# STM8_LQFP64_DEVELOPMENT_BOARD.net
KiCad netlist of a schematic drawn in Altium Designer
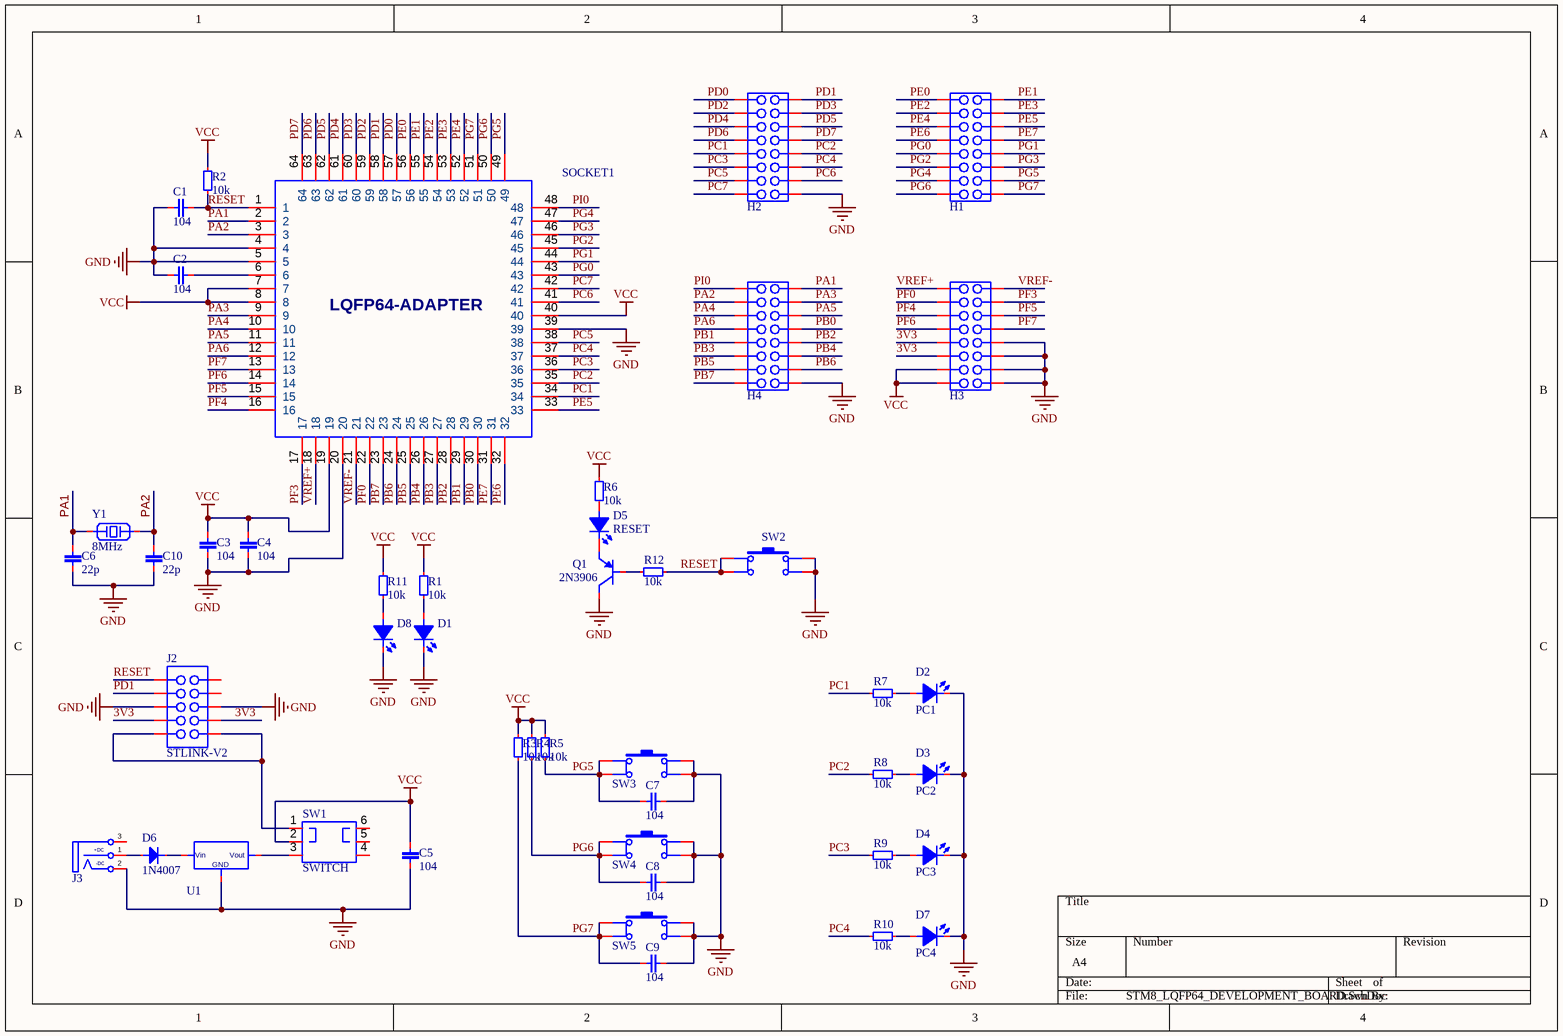
[diagram p0: STM8_LQFP64_DEVELOPMENT_BOARD.SchDoc]

(export (version "E")
  (design (tool "Eeschema 10.0.6"))
  (components
    (comp (ref "C1")
      (value "104")
      (footprint "C0805")
      (libsource (lib "MyAltiumLibrary") (part "Capacitors(SMD)"))
    )
    (comp (ref "C2")
      (value "104")
      (footprint "C0805")
      (libsource (lib "MyAltiumLibrary") (part "Capacitors(SMD)"))
    )
    (comp (ref "C3") (value "104") (footprint "C1812") (libsource (lib "") (part "Capacitors(SMD)_1")))
    (comp (ref "C4") (value "104") (footprint "C0805") (libsource (lib "") (part "Capacitors(SMD)_1")))
    (comp (ref "C5") (value "104") (footprint "C1812") (libsource (lib "") (part "Capacitors(SMD)_1")))
    (comp (ref "C6") (value "22p") (footprint "C0805") (libsource (lib "") (part "Capacitors(SMD)_1")))
    (comp (ref "C7")
      (value "104")
      (footprint "C0805")
      (libsource (lib "MyAltiumLibrary") (part "Capacitors(SMD)"))
    )
    (comp (ref "C8")
      (value "104")
      (footprint "C0805")
      (libsource (lib "MyAltiumLibrary") (part "Capacitors(SMD)"))
    )
    (comp (ref "C9")
      (value "104")
      (footprint "C0805")
      (libsource (lib "MyAltiumLibrary") (part "Capacitors(SMD)"))
    )
    (comp (ref "C10") (value "22p") (footprint "C0805") (libsource (lib "") (part "Capacitors(SMD)_1")))
    (comp (ref "D1")
      (value "POWER")
      (footprint "L0805RED")
      (libsource (lib "MyAltiumLibrary") (part "LED0805"))
    )
    (comp (ref "D2")
      (value "PC1")
      (footprint "L0805RED")
      (libsource (lib "MyAltiumLibrary") (part "LED0805"))
    )
    (comp (ref "D3")
      (value "PC2")
      (footprint "L0805RED")
      (libsource (lib "MyAltiumLibrary") (part "LED0805"))
    )
    (comp (ref "D4")
      (value "PC3")
      (footprint "L0805RED")
      (libsource (lib "MyAltiumLibrary") (part "LED0805"))
    )
    (comp (ref "D5")
      (value "RESET")
      (footprint "L0805RED")
      (libsource (lib "MyAltiumLibrary") (part "LED0805"))
    )
    (comp (ref "D6")
      (value "1N4007")
      (footprint "DO-214AC")
      (libsource (lib "MyAltiumLibrary") (part "Diode-1N4007"))
    )
    (comp (ref "D7")
      (value "PC4")
      (footprint "L0805RED")
      (libsource (lib "MyAltiumLibrary") (part "LED0805"))
    )
    (comp (ref "D8")
      (value "POWER")
      (footprint "L0805RED")
      (libsource (lib "MyAltiumLibrary") (part "LED0805"))
    )
    (comp (ref "H1")
      (value "HEADER-MALE-DOUBLE")
      (footprint "HEADER-MALE-DOUBLE-16PINS-2.54MM")
      (libsource (lib "MyAltiumLibrary") (part "HEADER-MALE-DOUBLE-16PINS-2.54MM"))
    )
    (comp (ref "H2")
      (value "HEADER-MALE-DOUBLE")
      (footprint "HEADER-MALE-DOUBLE-16PINS-2.54MM")
      (libsource (lib "MyAltiumLibrary") (part "HEADER-MALE-DOUBLE-16PINS-2.54MM"))
    )
    (comp (ref "H3")
      (value "HEADER-MALE-DOUBLE")
      (footprint "HEADER-MALE-DOUBLE-16PINS-2.54MM")
      (libsource (lib "MyAltiumLibrary") (part "HEADER-MALE-DOUBLE-16PINS-2.54MM"))
    )
    (comp (ref "H4")
      (value "HEADER-MALE-DOUBLE")
      (footprint "HEADER-MALE-DOUBLE-16PINS-2.54MM")
      (libsource (lib "MyAltiumLibrary") (part "HEADER-MALE-DOUBLE-16PINS-2.54MM"))
    )
    (comp (ref "J2")
      (value "STLINK-V2")
      (footprint "IDC_CONNECTOR_10x2.54")
      (libsource (lib "MyAltiumLibrary") (part "IDC_2.54_5x2"))
    )
    (comp (ref "J3")
      (value "Connector")
      (footprint "DC_K375A_Power")
      (libsource (lib "MyAltiumLibrary") (part "JackDC"))
    )
    (comp (ref "Q1")
      (value "2N3906")
      (footprint "SOT23-3")
      (libsource (lib "MyAltiumLibrary") (part "Transistor-2N3906 (SOT-23)"))
    )
    (comp (ref "R1") (value "10k") (footprint "R0805") (libsource (lib "") (part "Resistors-SMD_2")))
    (comp (ref "R2")
      (value "10k")
      (footprint "R0805")
      (libsource (lib "MyAltiumLibrary") (part "Resistors-SMD"))
    )
    (comp (ref "R3")
      (value "10k")
      (footprint "R0805")
      (libsource (lib "MyAltiumLibrary") (part "Resistors-SMD"))
    )
    (comp (ref "R4")
      (value "10k")
      (footprint "R0805")
      (libsource (lib "MyAltiumLibrary") (part "Resistors-SMD"))
    )
    (comp (ref "R5")
      (value "10k")
      (footprint "R0805")
      (libsource (lib "MyAltiumLibrary") (part "Resistors-SMD"))
    )
    (comp (ref "R6") (value "10k") (footprint "R0805") (libsource (lib "") (part "Resistors-SMD_2")))
    (comp (ref "R7") (value "10k") (footprint "R0805") (libsource (lib "") (part "Resistors-SMD_1")))
    (comp (ref "R8") (value "10k") (footprint "R0805") (libsource (lib "") (part "Resistors-SMD_1")))
    (comp (ref "R9") (value "10k") (footprint "R0805") (libsource (lib "") (part "Resistors-SMD_1")))
    (comp (ref "R10") (value "10k") (footprint "R0805") (libsource (lib "") (part "Resistors-SMD_1")))
    (comp (ref "R11") (value "10k") (footprint "R0805") (libsource (lib "") (part "Resistors-SMD_2")))
    (comp (ref "R12") (value "10k") (footprint "R0805") (libsource (lib "") (part "Resistors-SMD_1")))
    (comp (ref "SOCKET1")
      (value "STM8 MICROCONTROLLER")
      (footprint "SOCKET-ADAPTER-OTQ-64-05-03")
      (libsource (lib "MyAltiumLibrary") (part "Mcu-SOCKET-ADAPTER-OTQ-64-05-03"))
    )
    (comp (ref "SW1")
      (value "SWITCH")
      (footprint "SWITCH 5.8x5.8 6 PINS")
      (libsource (lib "MyAltiumLibrary") (part "SWITCH-DPDT"))
    )
    (comp (ref "SW2")
      (value "RESET")
      (footprint "BUTTON_HOLE_4.3mm")
      (libsource (lib "MyAltiumLibrary") (part "Button Hole"))
    )
    (comp (ref "SW3")
      (value "PG5")
      (footprint "BUTTON_HOLE_4.3mm")
      (libsource (lib "MyAltiumLibrary") (part "Button Hole"))
    )
    (comp (ref "SW4")
      (value "PG6")
      (footprint "BUTTON_HOLE_4.3mm")
      (libsource (lib "MyAltiumLibrary") (part "Button Hole"))
    )
    (comp (ref "SW5")
      (value "PG7")
      (footprint "BUTTON_HOLE_4.3mm")
      (libsource (lib "MyAltiumLibrary") (part "Button Hole"))
    )
    (comp (ref "U1")
      (value "AMS1117")
      (footprint "SOT223-3")
      (libsource (lib "MyAltiumLibrary") (part "Ic-AMS1117(SOT-223)"))
    )
    (comp (ref "Y1")
      (value "8MHz")
      (footprint "HC-49_THROUGH")
      (libsource (lib "MyAltiumLibrary") (part "Crystal"))
    )
  )
  (nets
    (net (code "1") (name "/3V3") (class "Default")
      (node (ref "H3") (pin "11") (pinfunction "11_11") (pintype "passive"))
      (node (ref "H3") (pin "9") (pinfunction "9_9") (pintype "passive"))
      (node (ref "J2") (pin "7") (pinfunction "7_7") (pintype "passive"))
      (node (ref "J2") (pin "8") (pinfunction "8_8") (pintype "passive"))
    )
    (net (code "2") (name "/PA1") (class "Default")
      (node (ref "C6") (pin "2") (pinfunction "2_2") (pintype "passive"))
      (node (ref "H4") (pin "2") (pinfunction "2_2") (pintype "passive"))
      (node (ref "SOCKET1") (pin "2") (pinfunction "2_2") (pintype "passive"))
      (node (ref "Y1") (pin "1") (pinfunction "1_1") (pintype "passive"))
    )
    (net (code "3") (name "/PA2") (class "Default")
      (node (ref "C10") (pin "2") (pinfunction "2_2") (pintype "passive"))
      (node (ref "H4") (pin "3") (pinfunction "3_3") (pintype "passive"))
      (node (ref "SOCKET1") (pin "3") (pinfunction "3_3") (pintype "passive"))
      (node (ref "Y1") (pin "2") (pinfunction "2_2") (pintype "passive"))
    )
    (net (code "4") (name "/PA3") (class "Default")
      (node (ref "H4") (pin "4") (pinfunction "4_4") (pintype "passive"))
      (node (ref "SOCKET1") (pin "9") (pinfunction "9_9") (pintype "passive"))
    )
    (net (code "5") (name "/PA4") (class "Default")
      (node (ref "H4") (pin "5") (pinfunction "5_5") (pintype "passive"))
      (node (ref "SOCKET1") (pin "10") (pinfunction "10_10") (pintype "passive"))
    )
    (net (code "6") (name "/PA5") (class "Default")
      (node (ref "H4") (pin "6") (pinfunction "6_6") (pintype "passive"))
      (node (ref "SOCKET1") (pin "11") (pinfunction "11_11") (pintype "passive"))
    )
    (net (code "7") (name "/PA6") (class "Default")
      (node (ref "H4") (pin "7") (pinfunction "7_7") (pintype "passive"))
      (node (ref "SOCKET1") (pin "12") (pinfunction "12_12") (pintype "passive"))
    )
    (net (code "8") (name "/PB0") (class "Default")
      (node (ref "H4") (pin "8") (pinfunction "8_8") (pintype "passive"))
      (node (ref "SOCKET1") (pin "30") (pinfunction "30_30") (pintype "passive"))
    )
    (net (code "9") (name "/PB1") (class "Default")
      (node (ref "H4") (pin "9") (pinfunction "9_9") (pintype "passive"))
      (node (ref "SOCKET1") (pin "29") (pinfunction "29_29") (pintype "passive"))
    )
    (net (code "10") (name "/PB2") (class "Default")
      (node (ref "H4") (pin "10") (pinfunction "10_10") (pintype "passive"))
      (node (ref "SOCKET1") (pin "28") (pinfunction "28_28") (pintype "passive"))
    )
    (net (code "11") (name "/PB3") (class "Default")
      (node (ref "H4") (pin "11") (pinfunction "11_11") (pintype "passive"))
      (node (ref "SOCKET1") (pin "27") (pinfunction "27_27") (pintype "passive"))
    )
    (net (code "12") (name "/PB4") (class "Default")
      (node (ref "H4") (pin "12") (pinfunction "12_12") (pintype "passive"))
      (node (ref "SOCKET1") (pin "26") (pinfunction "26_26") (pintype "passive"))
    )
    (net (code "13") (name "/PB5") (class "Default")
      (node (ref "H4") (pin "13") (pinfunction "13_13") (pintype "passive"))
      (node (ref "SOCKET1") (pin "25") (pinfunction "25_25") (pintype "passive"))
    )
    (net (code "14") (name "/PB6") (class "Default")
      (node (ref "H4") (pin "14") (pinfunction "14_14") (pintype "passive"))
      (node (ref "SOCKET1") (pin "24") (pinfunction "24_24") (pintype "passive"))
    )
    (net (code "15") (name "/PB7") (class "Default")
      (node (ref "H4") (pin "15") (pinfunction "15_15") (pintype "passive"))
      (node (ref "SOCKET1") (pin "23") (pinfunction "23_23") (pintype "passive"))
    )
    (net (code "16") (name "/PC1") (class "Default")
      (node (ref "H2") (pin "9") (pinfunction "9_9") (pintype "passive"))
      (node (ref "R7") (pin "2") (pinfunction "2_2") (pintype "passive"))
      (node (ref "SOCKET1") (pin "34") (pinfunction "34_34") (pintype "passive"))
    )
    (net (code "17") (name "/PC2") (class "Default")
      (node (ref "H2") (pin "10") (pinfunction "10_10") (pintype "passive"))
      (node (ref "R8") (pin "2") (pinfunction "2_2") (pintype "passive"))
      (node (ref "SOCKET1") (pin "35") (pinfunction "35_35") (pintype "passive"))
    )
    (net (code "18") (name "/PC3") (class "Default")
      (node (ref "H2") (pin "11") (pinfunction "11_11") (pintype "passive"))
      (node (ref "R9") (pin "2") (pinfunction "2_2") (pintype "passive"))
      (node (ref "SOCKET1") (pin "36") (pinfunction "36_36") (pintype "passive"))
    )
    (net (code "19") (name "/PC4") (class "Default")
      (node (ref "H2") (pin "12") (pinfunction "12_12") (pintype "passive"))
      (node (ref "R10") (pin "2") (pinfunction "2_2") (pintype "passive"))
      (node (ref "SOCKET1") (pin "37") (pinfunction "37_37") (pintype "passive"))
    )
    (net (code "20") (name "/PC5") (class "Default")
      (node (ref "H2") (pin "13") (pinfunction "13_13") (pintype "passive"))
      (node (ref "SOCKET1") (pin "38") (pinfunction "38_38") (pintype "passive"))
    )
    (net (code "21") (name "/PC6") (class "Default")
      (node (ref "H2") (pin "14") (pinfunction "14_14") (pintype "passive"))
      (node (ref "SOCKET1") (pin "41") (pinfunction "41_41") (pintype "passive"))
    )
    (net (code "22") (name "/PC7") (class "Default")
      (node (ref "H2") (pin "15") (pinfunction "15_15") (pintype "passive"))
      (node (ref "SOCKET1") (pin "42") (pinfunction "42_42") (pintype "passive"))
    )
    (net (code "23") (name "/PD0") (class "Default")
      (node (ref "H2") (pin "1") (pinfunction "1_1") (pintype "passive"))
      (node (ref "SOCKET1") (pin "57") (pinfunction "57_57") (pintype "passive"))
    )
    (net (code "24") (name "/PD1") (class "Default")
      (node (ref "H2") (pin "2") (pinfunction "2_2") (pintype "passive"))
      (node (ref "J2") (pin "3") (pinfunction "3_3") (pintype "passive"))
      (node (ref "SOCKET1") (pin "58") (pinfunction "58_58") (pintype "passive"))
    )
    (net (code "25") (name "/PD2") (class "Default")
      (node (ref "H2") (pin "3") (pinfunction "3_3") (pintype "passive"))
      (node (ref "SOCKET1") (pin "59") (pinfunction "59_59") (pintype "passive"))
    )
    (net (code "26") (name "/PD3") (class "Default")
      (node (ref "H2") (pin "4") (pinfunction "4_4") (pintype "passive"))
      (node (ref "SOCKET1") (pin "60") (pinfunction "60_60") (pintype "passive"))
    )
    (net (code "27") (name "/PD4") (class "Default")
      (node (ref "H2") (pin "5") (pinfunction "5_5") (pintype "passive"))
      (node (ref "SOCKET1") (pin "61") (pinfunction "61_61") (pintype "passive"))
    )
    (net (code "28") (name "/PD5") (class "Default")
      (node (ref "H2") (pin "6") (pinfunction "6_6") (pintype "passive"))
      (node (ref "SOCKET1") (pin "62") (pinfunction "62_62") (pintype "passive"))
    )
    (net (code "29") (name "/PD6") (class "Default")
      (node (ref "H2") (pin "7") (pinfunction "7_7") (pintype "passive"))
      (node (ref "SOCKET1") (pin "63") (pinfunction "63_63") (pintype "passive"))
    )
    (net (code "30") (name "/PD7") (class "Default")
      (node (ref "H2") (pin "8") (pinfunction "8_8") (pintype "passive"))
      (node (ref "SOCKET1") (pin "64") (pinfunction "64_64") (pintype "passive"))
    )
    (net (code "31") (name "/PE0") (class "Default")
      (node (ref "H1") (pin "1") (pinfunction "1_1") (pintype "passive"))
      (node (ref "SOCKET1") (pin "56") (pinfunction "56_56") (pintype "passive"))
    )
    (net (code "32") (name "/PE1") (class "Default")
      (node (ref "H1") (pin "2") (pinfunction "2_2") (pintype "passive"))
      (node (ref "SOCKET1") (pin "55") (pinfunction "55_55") (pintype "passive"))
    )
    (net (code "33") (name "/PE2") (class "Default")
      (node (ref "H1") (pin "3") (pinfunction "3_3") (pintype "passive"))
      (node (ref "SOCKET1") (pin "54") (pinfunction "54_54") (pintype "passive"))
    )
    (net (code "34") (name "/PE3") (class "Default")
      (node (ref "H1") (pin "4") (pinfunction "4_4") (pintype "passive"))
      (node (ref "SOCKET1") (pin "53") (pinfunction "53_53") (pintype "passive"))
    )
    (net (code "35") (name "/PE4") (class "Default")
      (node (ref "H1") (pin "5") (pinfunction "5_5") (pintype "passive"))
      (node (ref "SOCKET1") (pin "52") (pinfunction "52_52") (pintype "passive"))
    )
    (net (code "36") (name "/PE5") (class "Default")
      (node (ref "H1") (pin "6") (pinfunction "6_6") (pintype "passive"))
      (node (ref "SOCKET1") (pin "33") (pinfunction "33_33") (pintype "passive"))
    )
    (net (code "37") (name "/PE6") (class "Default")
      (node (ref "H1") (pin "7") (pinfunction "7_7") (pintype "passive"))
      (node (ref "SOCKET1") (pin "32") (pinfunction "32_32") (pintype "passive"))
    )
    (net (code "38") (name "/PE7") (class "Default")
      (node (ref "H1") (pin "8") (pinfunction "8_8") (pintype "passive"))
      (node (ref "SOCKET1") (pin "31") (pinfunction "31_31") (pintype "passive"))
    )
    (net (code "39") (name "/PF0") (class "Default")
      (node (ref "H3") (pin "3") (pinfunction "3_3") (pintype "passive"))
      (node (ref "SOCKET1") (pin "22") (pinfunction "22_22") (pintype "passive"))
    )
    (net (code "40") (name "/PF3") (class "Default")
      (node (ref "H3") (pin "4") (pinfunction "4_4") (pintype "passive"))
      (node (ref "SOCKET1") (pin "17") (pinfunction "17_17") (pintype "passive"))
    )
    (net (code "41") (name "/PF4") (class "Default")
      (node (ref "H3") (pin "5") (pinfunction "5_5") (pintype "passive"))
      (node (ref "SOCKET1") (pin "16") (pinfunction "16_16") (pintype "passive"))
    )
    (net (code "42") (name "/PF5") (class "Default")
      (node (ref "H3") (pin "6") (pinfunction "6_6") (pintype "passive"))
      (node (ref "SOCKET1") (pin "15") (pinfunction "15_15") (pintype "passive"))
    )
    (net (code "43") (name "/PF6") (class "Default")
      (node (ref "H3") (pin "7") (pinfunction "7_7") (pintype "passive"))
      (node (ref "SOCKET1") (pin "14") (pinfunction "14_14") (pintype "passive"))
    )
    (net (code "44") (name "/PF7") (class "Default")
      (node (ref "H3") (pin "8") (pinfunction "8_8") (pintype "passive"))
      (node (ref "SOCKET1") (pin "13") (pinfunction "13_13") (pintype "passive"))
    )
    (net (code "45") (name "/PG0") (class "Default")
      (node (ref "H1") (pin "9") (pinfunction "9_9") (pintype "passive"))
      (node (ref "SOCKET1") (pin "43") (pinfunction "43_43") (pintype "passive"))
    )
    (net (code "46") (name "/PG1") (class "Default")
      (node (ref "H1") (pin "10") (pinfunction "10_10") (pintype "passive"))
      (node (ref "SOCKET1") (pin "44") (pinfunction "44_44") (pintype "passive"))
    )
    (net (code "47") (name "/PG2") (class "Default")
      (node (ref "H1") (pin "11") (pinfunction "11_11") (pintype "passive"))
      (node (ref "SOCKET1") (pin "45") (pinfunction "45_45") (pintype "passive"))
    )
    (net (code "48") (name "/PG3") (class "Default")
      (node (ref "H1") (pin "12") (pinfunction "12_12") (pintype "passive"))
      (node (ref "SOCKET1") (pin "46") (pinfunction "46_46") (pintype "passive"))
    )
    (net (code "49") (name "/PG4") (class "Default")
      (node (ref "H1") (pin "13") (pinfunction "13_13") (pintype "passive"))
      (node (ref "SOCKET1") (pin "47") (pinfunction "47_47") (pintype "passive"))
    )
    (net (code "50") (name "/PG5") (class "Default")
      (node (ref "C7") (pin "1") (pinfunction "1_1") (pintype "passive"))
      (node (ref "H1") (pin "14") (pinfunction "14_14") (pintype "passive"))
      (node (ref "R5") (pin "2") (pinfunction "2_2") (pintype "passive"))
      (node (ref "SOCKET1") (pin "49") (pinfunction "49_49") (pintype "passive"))
      (node (ref "SW3") (pin "1") (pinfunction "1_1") (pintype "passive"))
      (node (ref "SW3") (pin "2") (pinfunction "2_2") (pintype "passive"))
    )
    (net (code "51") (name "/PG6") (class "Default")
      (node (ref "C8") (pin "1") (pinfunction "1_1") (pintype "passive"))
      (node (ref "H1") (pin "15") (pinfunction "15_15") (pintype "passive"))
      (node (ref "R4") (pin "2") (pinfunction "2_2") (pintype "passive"))
      (node (ref "SOCKET1") (pin "50") (pinfunction "50_50") (pintype "passive"))
      (node (ref "SW4") (pin "1") (pinfunction "1_1") (pintype "passive"))
      (node (ref "SW4") (pin "2") (pinfunction "2_2") (pintype "passive"))
    )
    (net (code "52") (name "/PG7") (class "Default")
      (node (ref "C9") (pin "1") (pinfunction "1_1") (pintype "passive"))
      (node (ref "H1") (pin "16") (pinfunction "16_16") (pintype "passive"))
      (node (ref "R3") (pin "2") (pinfunction "2_2") (pintype "passive"))
      (node (ref "SOCKET1") (pin "51") (pinfunction "51_51") (pintype "passive"))
      (node (ref "SW5") (pin "1") (pinfunction "1_1") (pintype "passive"))
      (node (ref "SW5") (pin "2") (pinfunction "2_2") (pintype "passive"))
    )
    (net (code "53") (name "/PI0") (class "Default")
      (node (ref "H4") (pin "1") (pinfunction "1_1") (pintype "passive"))
      (node (ref "SOCKET1") (pin "48") (pinfunction "48_48") (pintype "passive"))
    )
    (net (code "54") (name "/RESET") (class "Default")
      (node (ref "C1") (pin "2") (pinfunction "2_2") (pintype "passive"))
      (node (ref "J2") (pin "1") (pinfunction "1_1") (pintype "passive"))
      (node (ref "R12") (pin "1") (pinfunction "1_1") (pintype "passive"))
      (node (ref "R2") (pin "2") (pinfunction "2_2") (pintype "passive"))
      (node (ref "SOCKET1") (pin "1") (pinfunction "1_1") (pintype "passive"))
      (node (ref "SW2") (pin "1") (pinfunction "1_1") (pintype "passive"))
      (node (ref "SW2") (pin "2") (pinfunction "2_2") (pintype "passive"))
    )
    (net (code "55") (name "/VREF+") (class "Default")
      (node (ref "H3") (pin "1") (pinfunction "1_1") (pintype "passive"))
      (node (ref "SOCKET1") (pin "18") (pinfunction "18_18") (pintype "passive"))
    )
    (net (code "56") (name "/VREF-") (class "Default")
      (node (ref "H3") (pin "2") (pinfunction "2_2") (pintype "passive"))
      (node (ref "SOCKET1") (pin "21") (pinfunction "21_21") (pintype "passive"))
    )
    (net (code "57") (name "GND") (class "Default")
      (node (ref "C1") (pin "1") (pinfunction "1_1") (pintype "passive"))
      (node (ref "C10") (pin "1") (pinfunction "1_1") (pintype "passive"))
      (node (ref "C2") (pin "1") (pinfunction "1_1") (pintype "passive"))
      (node (ref "C3") (pin "1") (pinfunction "1_1") (pintype "passive"))
      (node (ref "C4") (pin "1") (pinfunction "1_1") (pintype "passive"))
      (node (ref "C5") (pin "1") (pinfunction "1_1") (pintype "passive"))
      (node (ref "C6") (pin "1") (pinfunction "1_1") (pintype "passive"))
      (node (ref "C7") (pin "2") (pinfunction "2_2") (pintype "passive"))
      (node (ref "C8") (pin "2") (pinfunction "2_2") (pintype "passive"))
      (node (ref "C9") (pin "2") (pinfunction "2_2") (pintype "passive"))
      (node (ref "D1") (pin "2") (pinfunction "K_2") (pintype "passive"))
      (node (ref "D2") (pin "2") (pinfunction "K_2") (pintype "passive"))
      (node (ref "D3") (pin "2") (pinfunction "K_2") (pintype "passive"))
      (node (ref "D4") (pin "2") (pinfunction "K_2") (pintype "passive"))
      (node (ref "D7") (pin "2") (pinfunction "K_2") (pintype "passive"))
      (node (ref "D8") (pin "2") (pinfunction "K_2") (pintype "passive"))
      (node (ref "H2") (pin "16") (pinfunction "16_16") (pintype "passive"))
      (node (ref "H3") (pin "10") (pinfunction "10_10") (pintype "passive"))
      (node (ref "H3") (pin "12") (pinfunction "12_12") (pintype "passive"))
      (node (ref "H3") (pin "14") (pinfunction "14_14") (pintype "passive"))
      (node (ref "H3") (pin "16") (pinfunction "16_16") (pintype "passive"))
      (node (ref "H4") (pin "16") (pinfunction "16_16") (pintype "passive"))
      (node (ref "J2") (pin "5") (pinfunction "5_5") (pintype "passive"))
      (node (ref "J2") (pin "6") (pinfunction "6_6") (pintype "passive"))
      (node (ref "J3") (pin "2") (pinfunction "DC-_2") (pintype "passive"))
      (node (ref "Q1") (pin "3") (pinfunction "C_3") (pintype "passive"))
      (node (ref "SOCKET1") (pin "20") (pinfunction "20_20") (pintype "passive"))
      (node (ref "SOCKET1") (pin "39") (pinfunction "39_39") (pintype "passive"))
      (node (ref "SOCKET1") (pin "4") (pinfunction "4_4") (pintype "passive"))
      (node (ref "SOCKET1") (pin "5") (pinfunction "5_5") (pintype "passive"))
      (node (ref "SW2") (pin "3") (pinfunction "3_3") (pintype "passive"))
      (node (ref "SW2") (pin "4") (pinfunction "4_4") (pintype "passive"))
      (node (ref "SW3") (pin "3") (pinfunction "3_3") (pintype "passive"))
      (node (ref "SW3") (pin "4") (pinfunction "4_4") (pintype "passive"))
      (node (ref "SW4") (pin "3") (pinfunction "3_3") (pintype "passive"))
      (node (ref "SW4") (pin "4") (pinfunction "4_4") (pintype "passive"))
      (node (ref "SW5") (pin "3") (pinfunction "3_3") (pintype "passive"))
      (node (ref "SW5") (pin "4") (pinfunction "4_4") (pintype "passive"))
      (node (ref "U1") (pin "1") (pinfunction "1_1") (pintype "passive"))
    )
    (net (code "58") (name "Net-(C2-Pad2)") (class "Default")
      (node (ref "C2") (pin "2") (pinfunction "2_2") (pintype "passive"))
      (node (ref "SOCKET1") (pin "6") (pinfunction "6_6") (pintype "passive"))
    )
    (net (code "59") (name "Net-(D1-A)") (class "Default")
      (node (ref "D1") (pin "1") (pinfunction "A_1") (pintype "passive"))
      (node (ref "R1") (pin "1") (pinfunction "1_1") (pintype "passive"))
    )
    (net (code "60") (name "Net-(D2-A)") (class "Default")
      (node (ref "D2") (pin "1") (pinfunction "A_1") (pintype "passive"))
      (node (ref "R7") (pin "1") (pinfunction "1_1") (pintype "passive"))
    )
    (net (code "61") (name "Net-(D3-A)") (class "Default")
      (node (ref "D3") (pin "1") (pinfunction "A_1") (pintype "passive"))
      (node (ref "R8") (pin "1") (pinfunction "1_1") (pintype "passive"))
    )
    (net (code "62") (name "Net-(D4-A)") (class "Default")
      (node (ref "D4") (pin "1") (pinfunction "A_1") (pintype "passive"))
      (node (ref "R9") (pin "1") (pinfunction "1_1") (pintype "passive"))
    )
    (net (code "63") (name "Net-(D5-A)") (class "Default")
      (node (ref "D5") (pin "1") (pinfunction "A_1") (pintype "passive"))
      (node (ref "R6") (pin "1") (pinfunction "1_1") (pintype "passive"))
    )
    (net (code "64") (name "Net-(D5-K)") (class "Default")
      (node (ref "D5") (pin "2") (pinfunction "K_2") (pintype "passive"))
      (node (ref "Q1") (pin "2") (pinfunction "E_2") (pintype "passive"))
    )
    (net (code "65") (name "Net-(D6-Pad2)") (class "Default")
      (node (ref "D6") (pin "2") (pinfunction "2_2") (pintype "passive"))
      (node (ref "U1") (pin "3") (pinfunction "3_3") (pintype "passive"))
    )
    (net (code "66") (name "Net-(D7-A)") (class "Default")
      (node (ref "D7") (pin "1") (pinfunction "A_1") (pintype "passive"))
      (node (ref "R10") (pin "1") (pinfunction "1_1") (pintype "passive"))
    )
    (net (code "67") (name "Net-(D8-A)") (class "Default")
      (node (ref "D8") (pin "1") (pinfunction "A_1") (pintype "passive"))
      (node (ref "R11") (pin "1") (pinfunction "1_1") (pintype "passive"))
    )
    (net (code "68") (name "Net-(J2-Pad10)") (class "Default")
      (node (ref "J2") (pin "10") (pinfunction "10_10") (pintype "passive"))
      (node (ref "J2") (pin "9") (pinfunction "9_9") (pintype "passive"))
      (node (ref "SW1") (pin "1") (pinfunction "1_1") (pintype "passive"))
    )
    (net (code "69") (name "Net-(J3-DS+)") (class "Default")
      (node (ref "D6") (pin "1") (pinfunction "1_1") (pintype "passive"))
      (node (ref "J3") (pin "1") (pinfunction "DS+_1") (pintype "power_in"))
    )
    (net (code "70") (name "Net-(Q1-B)") (class "Default")
      (node (ref "Q1") (pin "1") (pinfunction "B_1") (pintype "passive"))
      (node (ref "R12") (pin "2") (pinfunction "2_2") (pintype "passive"))
    )
    (net (code "71") (name "Net-(SW1-Pad3)") (class "Default")
      (node (ref "SW1") (pin "3") (pinfunction "3_3") (pintype "passive"))
      (node (ref "U1") (pin "2") (pinfunction "2_2") (pintype "passive"))
    )
    (net (code "72") (name "VCC") (class "Default")
      (node (ref "C3") (pin "2") (pinfunction "2_2") (pintype "passive"))
      (node (ref "C4") (pin "2") (pinfunction "2_2") (pintype "passive"))
      (node (ref "C5") (pin "2") (pinfunction "2_2") (pintype "passive"))
      (node (ref "H3") (pin "13") (pinfunction "13_13") (pintype "passive"))
      (node (ref "H3") (pin "15") (pinfunction "15_15") (pintype "passive"))
      (node (ref "R1") (pin "2") (pinfunction "2_2") (pintype "passive"))
      (node (ref "R11") (pin "2") (pinfunction "2_2") (pintype "passive"))
      (node (ref "R2") (pin "1") (pinfunction "1_1") (pintype "passive"))
      (node (ref "R3") (pin "1") (pinfunction "1_1") (pintype "passive"))
      (node (ref "R4") (pin "1") (pinfunction "1_1") (pintype "passive"))
      (node (ref "R5") (pin "1") (pinfunction "1_1") (pintype "passive"))
      (node (ref "R6") (pin "2") (pinfunction "2_2") (pintype "passive"))
      (node (ref "SOCKET1") (pin "19") (pinfunction "19_19") (pintype "passive"))
      (node (ref "SOCKET1") (pin "40") (pinfunction "40_40") (pintype "passive"))
      (node (ref "SOCKET1") (pin "7") (pinfunction "7_7") (pintype "passive"))
      (node (ref "SOCKET1") (pin "8") (pinfunction "8_8") (pintype "passive"))
      (node (ref "SW1") (pin "2") (pinfunction "2_2") (pintype "passive"))
    )
    (net (code "73") (name "unconnected-(J2-Pad2)") (class "Default")
      (node (ref "J2") (pin "2") (pinfunction "2_2") (pintype "passive"))
    )
    (net (code "74") (name "unconnected-(J2-Pad4)") (class "Default")
      (node (ref "J2") (pin "4") (pinfunction "4_4") (pintype "passive"))
    )
    (net (code "75") (name "unconnected-(J3-T-Pad3)") (class "Default")
      (node (ref "J3") (pin "3") (pinfunction "T_3") (pintype "passive"))
    )
    (net (code "76") (name "unconnected-(SW1-Pad4)") (class "Default")
      (node (ref "SW1") (pin "4") (pinfunction "4_4") (pintype "passive"))
    )
    (net (code "77") (name "unconnected-(SW1-Pad5)") (class "Default")
      (node (ref "SW1") (pin "5") (pinfunction "5_5") (pintype "passive"))
    )
    (net (code "78") (name "unconnected-(SW1-Pad6)") (class "Default")
      (node (ref "SW1") (pin "6") (pinfunction "6_6") (pintype "passive"))
    )
  )
)
